# ESP32-Softub.net
KiCad netlist of a schematic drawn in EAGLE
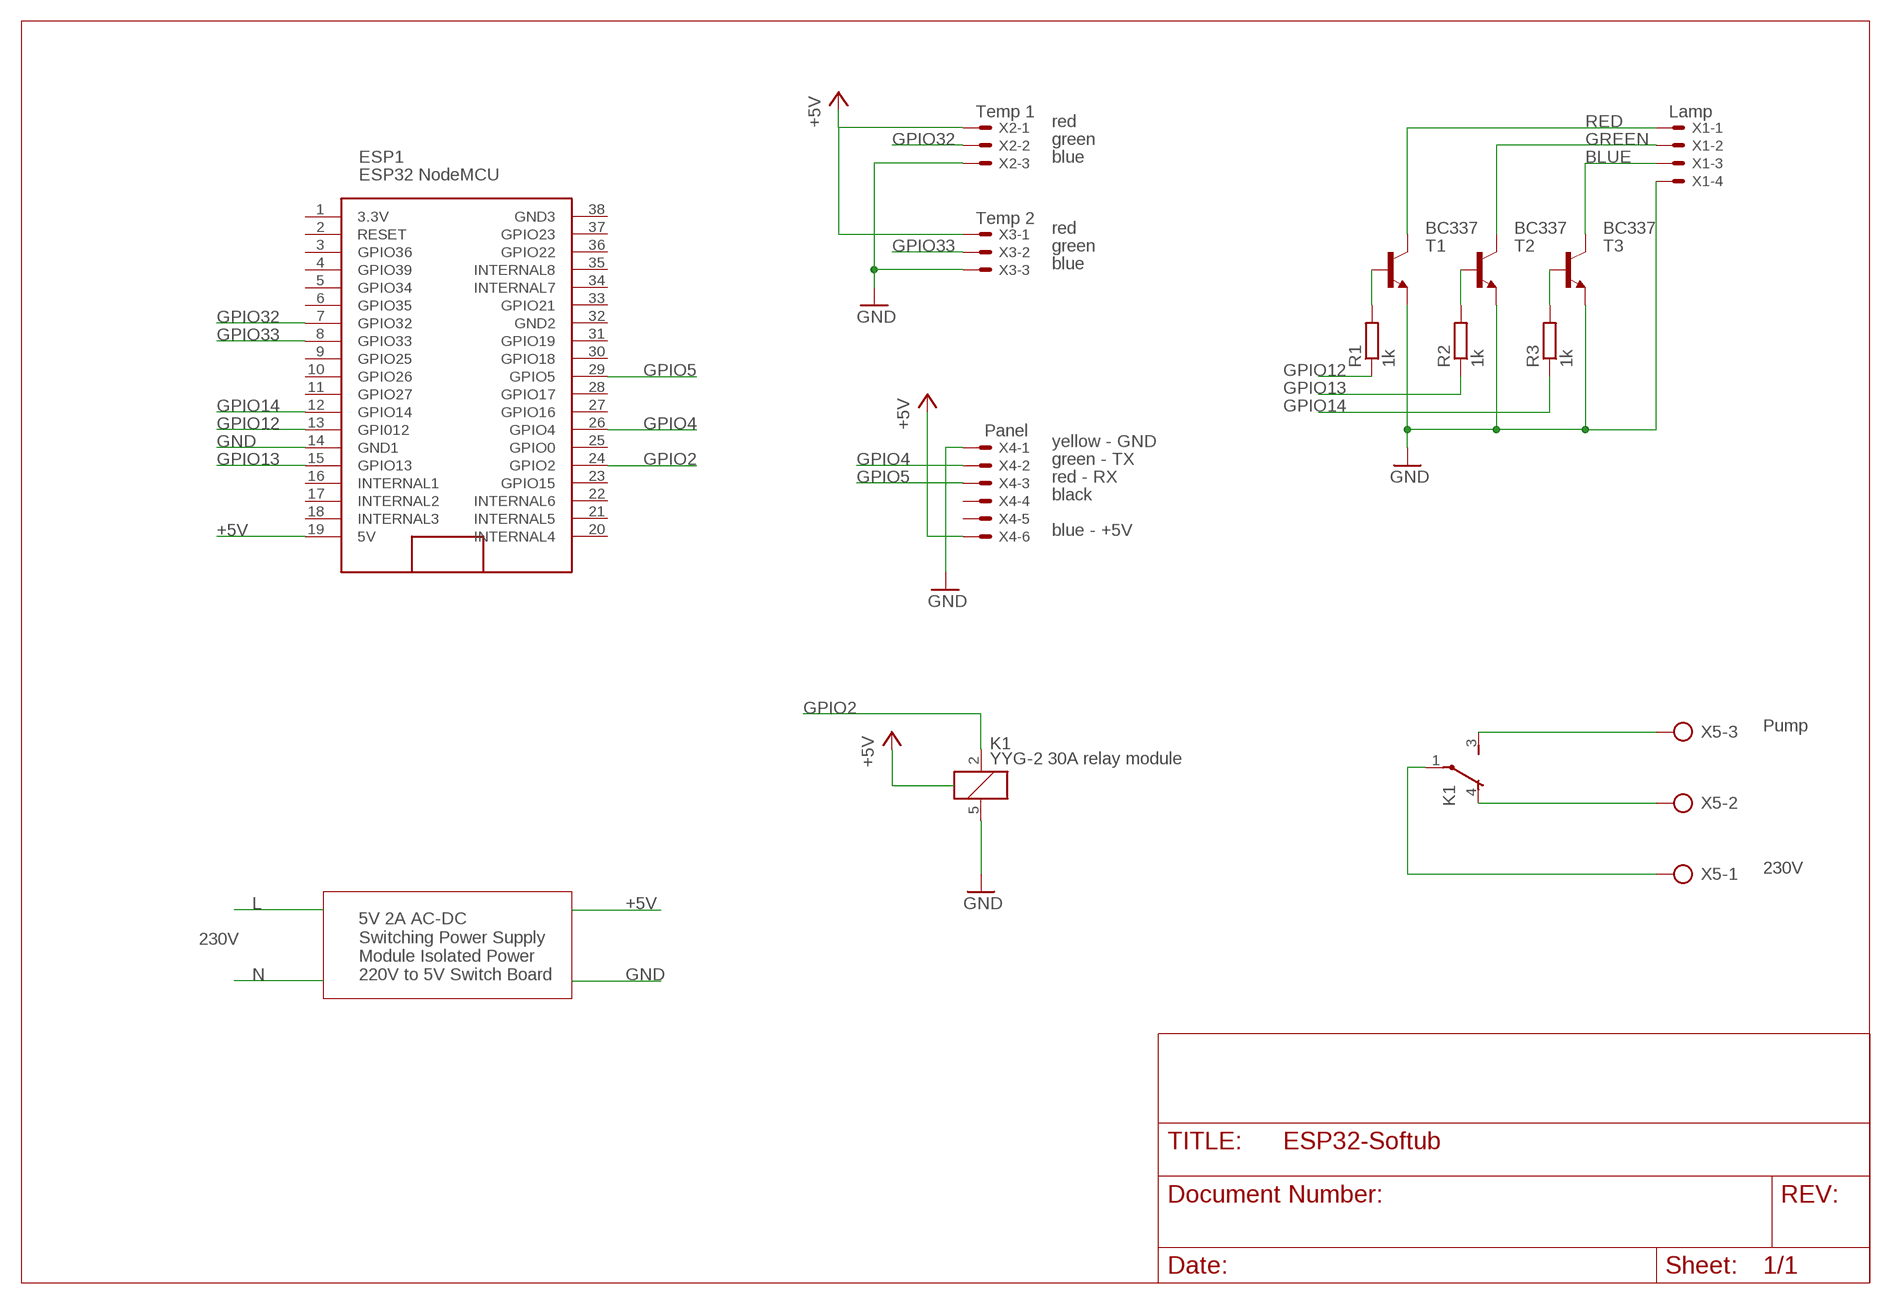
[diagram p0: schematic, sheet 1]

(export (version "E")
  (design (tool "Eeschema 10.0.6"))
  (components
    (comp (ref "ESP1")
      (value "ESP32 NodeMCU")
      (footprint "eagle-import:ESP32_NODEMCU")
      (libsource (lib "eagle-import") (part "ESP32-NODEMCU"))
    )
    (comp (ref "K1")
      (value "YYG-2 30A relay module")
      (footprint "eagle-import:AZ8")
      (libsource (lib "eagle-import") (part "AZ8-FORM-C"))
    )
    (comp (ref "R1")
      (value "1k")
      (footprint "eagle-import:0309_12")
      (libsource (lib "eagle-import") (part "R-EU_0309/12"))
    )
    (comp (ref "R2")
      (value "1k")
      (footprint "eagle-import:0309_12")
      (libsource (lib "eagle-import") (part "R-EU_0309/12"))
    )
    (comp (ref "R3")
      (value "1k")
      (footprint "eagle-import:0309_12")
      (libsource (lib "eagle-import") (part "R-EU_0309/12"))
    )
    (comp (ref "T1")
      (value "BC337")
      (footprint "eagle-import:TO92")
      (libsource (lib "eagle-import") (part "BC337"))
    )
    (comp (ref "T2")
      (value "BC337")
      (footprint "eagle-import:TO92")
      (libsource (lib "eagle-import") (part "BC337"))
    )
    (comp (ref "T3")
      (value "BC337")
      (footprint "eagle-import:TO92")
      (libsource (lib "eagle-import") (part "BC337"))
    )
    (comp (ref "X1")
      (value "Lamp")
      (footprint "eagle-import:22-23-2041")
      (fields (field (name "MF") "MOLEX") (field (name "MPN") "22-23-2041"))
      (libsource (lib "eagle-import") (part "22-23-2041"))
    )
    (comp (ref "X2")
      (value "Temp 1")
      (footprint "eagle-import:22-23-2031")
      (fields (field (name "MF") "MOLEX") (field (name "MPN") "22-23-2031"))
      (libsource (lib "eagle-import") (part "22-23-2031"))
    )
    (comp (ref "X3")
      (value "Temp 2")
      (footprint "eagle-import:22-23-2031")
      (fields (field (name "MF") "MOLEX") (field (name "MPN") "22-23-2031"))
      (libsource (lib "eagle-import") (part "22-23-2031"))
    )
    (comp (ref "X4")
      (value "22-23-2061")
      (footprint "eagle-import:22-23-2061")
      (fields (field (name "MF") "MOLEX"))
      (libsource (lib "eagle-import") (part "22-23-2061"))
    )
    (comp (ref "X5")
      (value "AK500/3")
      (footprint "eagle-import:AK500_3")
      (libsource (lib "eagle-import") (part "AK500/3"))
    )
  )
  (nets
    (net (code "1") (name "+5V") (class "Default")
      (node (ref "ESP1") (pin "19") (pinfunction "5V_19") (pintype "power_in"))
      (node (ref "X2") (pin "1") (pinfunction "S_1") (pintype "passive"))
      (node (ref "X3") (pin "1") (pinfunction "S_1") (pintype "passive"))
      (node (ref "X4") (pin "6") (pinfunction "S_6") (pintype "passive"))
    )
    (net (code "2") (name "/3.3V") (class "Default")
      (node (ref "ESP1") (pin "1") (pinfunction "3.3V_1") (pintype "power_in"))
    )
    (net (code "3") (name "/BLUE") (class "Default")
      (node (ref "T3") (pin "3") (pinfunction "C_3") (pintype "passive"))
      (node (ref "X1") (pin "3") (pinfunction "S_3") (pintype "passive"))
    )
    (net (code "4") (name "/GND2") (class "Default")
      (node (ref "ESP1") (pin "32") (pinfunction "GND2_32") (pintype "power_in"))
    )
    (net (code "5") (name "/GND3") (class "Default")
      (node (ref "ESP1") (pin "38") (pinfunction "GND3_38") (pintype "power_in"))
    )
    (net (code "6") (name "/GPIO2") (class "Default")
      (node (ref "ESP1") (pin "24") (pinfunction "GPIO2_24") (pintype "bidirectional"))
      (node (ref "K1") (pin "2") (pinfunction "1_2") (pintype "passive"))
    )
    (net (code "7") (name "/GPIO4") (class "Default")
      (node (ref "ESP1") (pin "26") (pinfunction "GPIO4_26") (pintype "bidirectional"))
      (node (ref "X4") (pin "2") (pinfunction "S_2") (pintype "passive"))
    )
    (net (code "8") (name "/GPIO5") (class "Default")
      (node (ref "ESP1") (pin "29") (pinfunction "GPIO5_29") (pintype "bidirectional"))
      (node (ref "X4") (pin "3") (pinfunction "S_3") (pintype "passive"))
    )
    (net (code "9") (name "/GPIO12") (class "Default")
      (node (ref "ESP1") (pin "13") (pinfunction "GPI012_13") (pintype "bidirectional"))
      (node (ref "R1") (pin "1") (pinfunction "1_1") (pintype "passive"))
    )
    (net (code "10") (name "/GPIO13") (class "Default")
      (node (ref "ESP1") (pin "15") (pinfunction "GPIO13_15") (pintype "bidirectional"))
      (node (ref "R2") (pin "1") (pinfunction "1_1") (pintype "passive"))
    )
    (net (code "11") (name "/GPIO14") (class "Default")
      (node (ref "ESP1") (pin "12") (pinfunction "GPIO14_12") (pintype "bidirectional"))
      (node (ref "R3") (pin "1") (pinfunction "1_1") (pintype "passive"))
    )
    (net (code "12") (name "/GPIO32") (class "Default")
      (node (ref "ESP1") (pin "7") (pinfunction "GPIO32_7") (pintype "bidirectional"))
      (node (ref "X2") (pin "2") (pinfunction "S_2") (pintype "passive"))
    )
    (net (code "13") (name "/GPIO33") (class "Default")
      (node (ref "ESP1") (pin "8") (pinfunction "GPIO33_8") (pintype "bidirectional"))
      (node (ref "X3") (pin "2") (pinfunction "S_2") (pintype "passive"))
    )
    (net (code "14") (name "/GREEN") (class "Default")
      (node (ref "T2") (pin "3") (pinfunction "C_3") (pintype "passive"))
      (node (ref "X1") (pin "2") (pinfunction "S_2") (pintype "passive"))
    )
    (net (code "17") (name "/RED") (class "Default")
      (node (ref "T1") (pin "3") (pinfunction "C_3") (pintype "passive"))
      (node (ref "X1") (pin "1") (pinfunction "S_1") (pintype "passive"))
    )
    (net (code "18") (name "GND") (class "Default")
      (node (ref "ESP1") (pin "14") (pinfunction "GND1_14") (pintype "power_in"))
      (node (ref "K1") (pin "5") (pinfunction "2_5") (pintype "passive"))
      (node (ref "T1") (pin "1") (pinfunction "E_1") (pintype "passive"))
      (node (ref "T2") (pin "1") (pinfunction "E_1") (pintype "passive"))
      (node (ref "T3") (pin "1") (pinfunction "E_1") (pintype "passive"))
      (node (ref "X1") (pin "4") (pinfunction "S_4") (pintype "passive"))
      (node (ref "X2") (pin "3") (pinfunction "S_3") (pintype "passive"))
      (node (ref "X3") (pin "3") (pinfunction "S_3") (pintype "passive"))
      (node (ref "X4") (pin "1") (pinfunction "S_1") (pintype "passive"))
    )
    (net (code "19") (name "Net-(K1A-O)") (class "Default")
      (node (ref "K1") (pin "4") (pinfunction "O_4") (pintype "passive"))
      (node (ref "X5") (pin "2") (pinfunction "KL_2") (pintype "passive"))
    )
    (net (code "20") (name "Net-(K1A-P)") (class "Default")
      (node (ref "K1") (pin "1") (pinfunction "P_1") (pintype "passive"))
      (node (ref "X5") (pin "1") (pinfunction "KL_1") (pintype "passive"))
    )
    (net (code "21") (name "Net-(K1A-S)") (class "Default")
      (node (ref "K1") (pin "3") (pinfunction "S_3") (pintype "passive"))
      (node (ref "X5") (pin "3") (pinfunction "KL_3") (pintype "passive"))
    )
    (net (code "22") (name "Net-(T1-B)") (class "Default")
      (node (ref "R1") (pin "2") (pinfunction "2_2") (pintype "passive"))
      (node (ref "T1") (pin "2") (pinfunction "B_2") (pintype "passive"))
    )
    (net (code "23") (name "Net-(T2-B)") (class "Default")
      (node (ref "R2") (pin "2") (pinfunction "2_2") (pintype "passive"))
      (node (ref "T2") (pin "2") (pinfunction "B_2") (pintype "passive"))
    )
    (net (code "24") (name "Net-(T3-B)") (class "Default")
      (node (ref "R3") (pin "2") (pinfunction "2_2") (pintype "passive"))
      (node (ref "T3") (pin "2") (pinfunction "B_2") (pintype "passive"))
    )
    (net (code "25") (name "unconnected-(ESP1-GPIO0-Pad25)") (class "Default")
      (node (ref "ESP1") (pin "25") (pinfunction "GPIO0_25") (pintype "output"))
    )
    (net (code "26") (name "unconnected-(ESP1-GPIO15-Pad23)") (class "Default")
      (node (ref "ESP1") (pin "23") (pinfunction "GPIO15_23") (pintype "bidirectional"))
    )
    (net (code "27") (name "unconnected-(ESP1-GPIO16-Pad27)") (class "Default")
      (node (ref "ESP1") (pin "27") (pinfunction "GPIO16_27") (pintype "bidirectional"))
    )
    (net (code "28") (name "unconnected-(ESP1-GPIO17-Pad28)") (class "Default")
      (node (ref "ESP1") (pin "28") (pinfunction "GPIO17_28") (pintype "bidirectional"))
    )
    (net (code "29") (name "unconnected-(ESP1-GPIO18-Pad30)") (class "Default")
      (node (ref "ESP1") (pin "30") (pinfunction "GPIO18_30") (pintype "bidirectional"))
    )
    (net (code "30") (name "unconnected-(ESP1-GPIO19-Pad31)") (class "Default")
      (node (ref "ESP1") (pin "31") (pinfunction "GPIO19_31") (pintype "bidirectional"))
    )
    (net (code "31") (name "unconnected-(ESP1-GPIO21-Pad33)") (class "Default")
      (node (ref "ESP1") (pin "33") (pinfunction "GPIO21_33") (pintype "bidirectional"))
    )
    (net (code "32") (name "unconnected-(ESP1-GPIO22-Pad36)") (class "Default")
      (node (ref "ESP1") (pin "36") (pinfunction "GPIO22_36") (pintype "bidirectional"))
    )
    (net (code "33") (name "unconnected-(ESP1-GPIO23-Pad37)") (class "Default")
      (node (ref "ESP1") (pin "37") (pinfunction "GPIO23_37") (pintype "bidirectional"))
    )
    (net (code "34") (name "unconnected-(ESP1-GPIO25-Pad9)") (class "Default")
      (node (ref "ESP1") (pin "9") (pinfunction "GPIO25_9") (pintype "bidirectional"))
    )
    (net (code "35") (name "unconnected-(ESP1-GPIO26-Pad10)") (class "Default")
      (node (ref "ESP1") (pin "10") (pinfunction "GPIO26_10") (pintype "bidirectional"))
    )
    (net (code "36") (name "unconnected-(ESP1-GPIO27-Pad11)") (class "Default")
      (node (ref "ESP1") (pin "11") (pinfunction "GPIO27_11") (pintype "bidirectional"))
    )
    (net (code "37") (name "unconnected-(ESP1-GPIO34-Pad5)") (class "Default")
      (node (ref "ESP1") (pin "5") (pinfunction "GPIO34_5") (pintype "input"))
    )
    (net (code "38") (name "unconnected-(ESP1-GPIO35-Pad6)") (class "Default")
      (node (ref "ESP1") (pin "6") (pinfunction "GPIO35_6") (pintype "input"))
    )
    (net (code "39") (name "unconnected-(ESP1-GPIO36-Pad3)") (class "Default")
      (node (ref "ESP1") (pin "3") (pinfunction "GPIO36_3") (pintype "input"))
    )
    (net (code "40") (name "unconnected-(ESP1-GPIO39-Pad4)") (class "Default")
      (node (ref "ESP1") (pin "4") (pinfunction "GPIO39_4") (pintype "input"))
    )
    (net (code "41") (name "unconnected-(ESP1-INTERNAL1-Pad16)") (class "Default")
      (node (ref "ESP1") (pin "16") (pinfunction "INTERNAL1_16") (pintype "no_connect"))
    )
    (net (code "42") (name "unconnected-(ESP1-INTERNAL2-Pad17)") (class "Default")
      (node (ref "ESP1") (pin "17") (pinfunction "INTERNAL2_17") (pintype "no_connect"))
    )
    (net (code "43") (name "unconnected-(ESP1-INTERNAL3-Pad18)") (class "Default")
      (node (ref "ESP1") (pin "18") (pinfunction "INTERNAL3_18") (pintype "no_connect"))
    )
    (net (code "44") (name "unconnected-(ESP1-INTERNAL4-Pad20)") (class "Default")
      (node (ref "ESP1") (pin "20") (pinfunction "INTERNAL4_20") (pintype "no_connect"))
    )
    (net (code "45") (name "unconnected-(ESP1-INTERNAL5-Pad21)") (class "Default")
      (node (ref "ESP1") (pin "21") (pinfunction "INTERNAL5_21") (pintype "no_connect"))
    )
    (net (code "46") (name "unconnected-(ESP1-INTERNAL6-Pad22)") (class "Default")
      (node (ref "ESP1") (pin "22") (pinfunction "INTERNAL6_22") (pintype "no_connect"))
    )
    (net (code "47") (name "unconnected-(ESP1-INTERNAL7-Pad34)") (class "Default")
      (node (ref "ESP1") (pin "34") (pinfunction "INTERNAL7_34") (pintype "no_connect"))
    )
    (net (code "48") (name "unconnected-(ESP1-INTERNAL8-Pad35)") (class "Default")
      (node (ref "ESP1") (pin "35") (pinfunction "INTERNAL8_35") (pintype "no_connect"))
    )
    (net (code "49") (name "unconnected-(ESP1-RESET-Pad2)") (class "Default")
      (node (ref "ESP1") (pin "2") (pinfunction "RESET_2") (pintype "input"))
    )
    (net (code "50") (name "unconnected-(X4D-S-Pad4)") (class "Default")
      (node (ref "X4") (pin "4") (pinfunction "S_4") (pintype "passive"))
    )
    (net (code "51") (name "unconnected-(X4E-S-Pad5)") (class "Default")
      (node (ref "X4") (pin "5") (pinfunction "S_5") (pintype "passive"))
    )
  )
)
